# 1_8inch-tft-display.net
KiCad netlist of a schematic drawn in Altium Designer
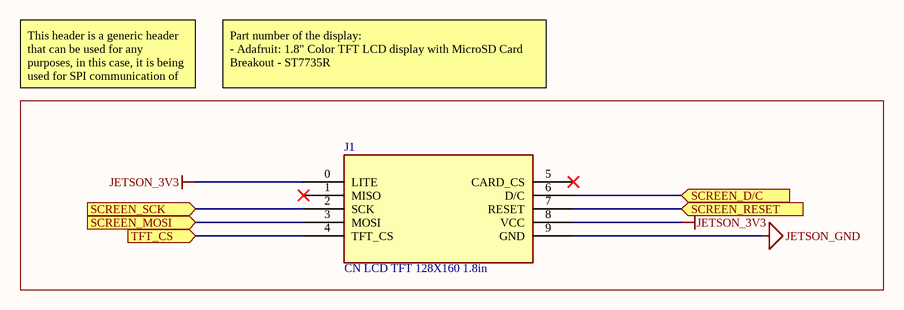
[diagram p0: 1.8inch-tft-display.SchDoc]

(export (version "E")
  (design (tool "Eeschema 10.0.6"))
  (components
    (comp (ref "J1")
      (value "CN LCD TFT 128X160 1.8in")
      (footprint "CN LCD TFT 128X160 1.8")
      (libsource (lib "Connector_Library") (part "CN LCD TFT 128X160 1.8in"))
    )
  )
  (nets
    (net (code "1") (name "/SCREEN_D{slash}C") (class "Default")
      (node (ref "J1") (pin "6") (pinfunction "D/C_6") (pintype "passive"))
    )
    (net (code "2") (name "/SCREEN_MOSI") (class "Default")
      (node (ref "J1") (pin "3") (pinfunction "MOSI_3") (pintype "passive"))
    )
    (net (code "3") (name "/SCREEN_RESET") (class "Default")
      (node (ref "J1") (pin "7") (pinfunction "RESET_7") (pintype "passive"))
    )
    (net (code "4") (name "/SCREEN_SCK") (class "Default")
      (node (ref "J1") (pin "2") (pinfunction "SCK_2") (pintype "passive"))
    )
    (net (code "5") (name "/TFT_CS") (class "Default")
      (node (ref "J1") (pin "4") (pinfunction "TFT_CS_4") (pintype "passive"))
    )
    (net (code "6") (name "JETSON_3V3") (class "Default")
      (node (ref "J1") (pin "0") (pinfunction "LITE_0") (pintype "passive"))
      (node (ref "J1") (pin "8") (pinfunction "VCC_8") (pintype "passive"))
    )
    (net (code "7") (name "JETSON_GND") (class "Default")
      (node (ref "J1") (pin "9") (pinfunction "GND_9") (pintype "passive"))
    )
    (net (code "8") (name "unconnected-(J1-CARD_CS-Pad5)") (class "Default")
      (node (ref "J1") (pin "5") (pinfunction "CARD_CS_5") (pintype "passive+no_connect"))
    )
    (net (code "9") (name "unconnected-(J1-MISO-Pad1)") (class "Default")
      (node (ref "J1") (pin "1") (pinfunction "MISO_1") (pintype "passive+no_connect"))
    )
  )
)
